# SterUni_V1.net
KiCad netlist of a schematic drawn in Altium Designer
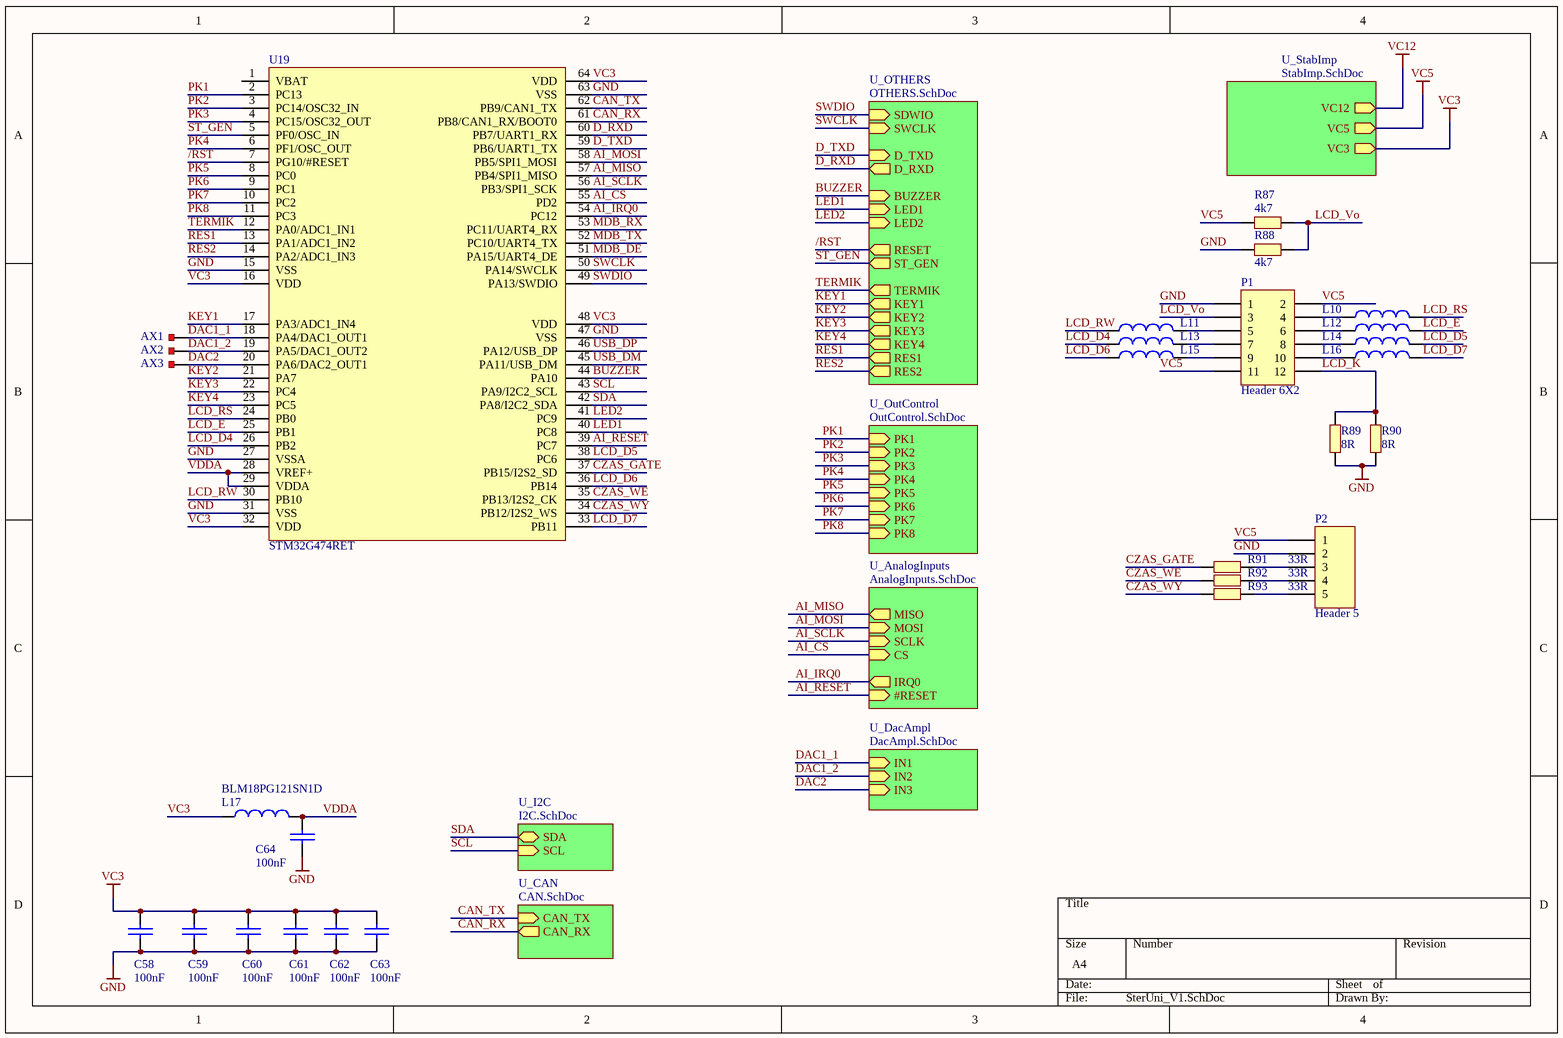
[diagram p0: SterUni_V1.SchDoc]

(export (version "E")
  (design (tool "Eeschema 10.0.6"))
  (components
    (comp (ref "AX1") (value "~") (footprint "PP_SMD4") (libsource (lib "*") (part "PP_RT")))
    (comp (ref "AX2") (value "~") (footprint "PP_SMD4") (libsource (lib "*") (part "PP_RT")))
    (comp (ref "AX3") (value "~") (footprint "PP_SMD4") (libsource (lib "*") (part "PP_RT")))
    (comp (ref "C58")
      (value "100nF")
      (footprint "0603C")
      (description "Capacitor")
      (libsource (lib "*") (part "CAP"))
    )
    (comp (ref "C59")
      (value "100nF")
      (footprint "0603C")
      (description "Capacitor")
      (libsource (lib "*") (part "CAP"))
    )
    (comp (ref "C60")
      (value "100nF")
      (footprint "0603C")
      (description "Capacitor")
      (libsource (lib "*") (part "CAP"))
    )
    (comp (ref "C61")
      (value "100nF")
      (footprint "0603C")
      (description "Capacitor")
      (libsource (lib "*") (part "CAP"))
    )
    (comp (ref "C62")
      (value "100nF")
      (footprint "0603C")
      (description "Capacitor")
      (libsource (lib "*") (part "CAP"))
    )
    (comp (ref "C63")
      (value "100nF")
      (footprint "0603C")
      (description "Capacitor")
      (libsource (lib "*") (part "CAP"))
    )
    (comp (ref "C64")
      (value "100nF")
      (footprint "0603C")
      (description "Capacitor")
      (libsource (lib "*") (part "CAP"))
    )
    (comp (ref "L10")
      (value "BLM18PG121SN1D")
      (footprint "0603L")
      (description "Bead,120R,2A,0603,BLM18PG121SN1D,MURATA")
      (libsource (lib "MCD_TOOLS") (part "BEAD_120R_2A_0603"))
    )
    (comp (ref "L11")
      (value "BLM18PG121SN1D")
      (footprint "0603L")
      (description "Bead,120R,2A,0603,BLM18PG121SN1D,MURATA")
      (libsource (lib "MCD_TOOLS") (part "BEAD_120R_2A_0603"))
    )
    (comp (ref "L12")
      (value "BLM18PG121SN1D")
      (footprint "0603L")
      (description "Bead,120R,2A,0603,BLM18PG121SN1D,MURATA")
      (libsource (lib "MCD_TOOLS") (part "BEAD_120R_2A_0603"))
    )
    (comp (ref "L13")
      (value "BLM18PG121SN1D")
      (footprint "0603L")
      (description "Bead,120R,2A,0603,BLM18PG121SN1D,MURATA")
      (libsource (lib "MCD_TOOLS") (part "BEAD_120R_2A_0603"))
    )
    (comp (ref "L14")
      (value "BLM18PG121SN1D")
      (footprint "0603L")
      (description "Bead,120R,2A,0603,BLM18PG121SN1D,MURATA")
      (libsource (lib "MCD_TOOLS") (part "BEAD_120R_2A_0603"))
    )
    (comp (ref "L15")
      (value "BLM18PG121SN1D")
      (footprint "0603L")
      (description "Bead,120R,2A,0603,BLM18PG121SN1D,MURATA")
      (libsource (lib "MCD_TOOLS") (part "BEAD_120R_2A_0603"))
    )
    (comp (ref "L16")
      (value "BLM18PG121SN1D")
      (footprint "0603L")
      (description "Bead,120R,2A,0603,BLM18PG121SN1D,MURATA")
      (libsource (lib "MCD_TOOLS") (part "BEAD_120R_2A_0603"))
    )
    (comp (ref "L17")
      (value "BLM18PG121SN1D")
      (footprint "0603L")
      (description "Bead,120R,2A,0603,BLM18PG121SN1D,MURATA")
      (libsource (lib "MCD_TOOLS") (part "BEAD_120R_2A_0603"))
    )
    (comp (ref "P1")
      (value "Header 6X2")
      (footprint "UMATCH-12")
      (description "Header, 6-Pin, Dual row")
      (fields (field (name "PUBLISHER") "Altium Limited"))
      (libsource (lib "Miscellaneous Connectors") (part "Header 6X2"))
    )
    (comp (ref "P2")
      (value "Header 5")
      (footprint "JST-B5B-XH-A")
      (description "Header, 5-Pin")
      (fields (field (name "PUBLISHER") "Altium Limited"))
      (libsource (lib "Miscellaneous Connectors") (part "Header 5"))
    )
    (comp (ref "R87") (value "4k7") (footprint "0603R") (libsource (lib "*") (part "RES3")))
    (comp (ref "R88") (value "4k7") (footprint "0603R") (libsource (lib "*") (part "RES3")))
    (comp (ref "R89") (value "8R") (footprint "1206") (libsource (lib "") (part "RES3_1")))
    (comp (ref "R90") (value "8R") (footprint "1206") (libsource (lib "") (part "RES3_1")))
    (comp (ref "R91") (value "33R") (footprint "0603R") (libsource (lib "*") (part "RES3")))
    (comp (ref "R92") (value "33R") (footprint "0603R") (libsource (lib "*") (part "RES3")))
    (comp (ref "R93") (value "33R") (footprint "0603R") (libsource (lib "*") (part "RES3")))
    (comp (ref "U19")
      (value "STM32G474RET")
      (footprint "LQFP64")
      (libsource (lib "GkSchlib") (part "STM32FG474RET"))
    )
  )
  (nets
    (net (code "1") (name "/AI_CS") (class "Default")
      (node (ref "U19") (pin "55") (pinfunction "PD2_55") (pintype "passive"))
    )
    (net (code "2") (name "/AI_IRQ0") (class "Default")
      (node (ref "U19") (pin "54") (pinfunction "PC12_54") (pintype "passive"))
    )
    (net (code "3") (name "/AI_MISO") (class "Default")
      (node (ref "U19") (pin "57") (pinfunction "PB4/SPI1_MISO_57") (pintype "passive"))
    )
    (net (code "4") (name "/AI_MOSI") (class "Default")
      (node (ref "U19") (pin "58") (pinfunction "PB5/SPI1_MOSI_58") (pintype "passive"))
    )
    (net (code "5") (name "/AI_RESET") (class "Default")
      (node (ref "U19") (pin "39") (pinfunction "PC7_39") (pintype "passive"))
    )
    (net (code "6") (name "/AI_SCLK") (class "Default")
      (node (ref "U19") (pin "56") (pinfunction "PB3/SPI1_SCK_56") (pintype "passive"))
    )
    (net (code "7") (name "/BUZZER") (class "Default")
      (node (ref "U19") (pin "44") (pinfunction "PA10_44") (pintype "passive"))
    )
    (net (code "8") (name "/CAN_RX") (class "Default")
      (node (ref "U19") (pin "61") (pinfunction "PB8/CAN1_RX/BOOT0_61") (pintype "passive"))
    )
    (net (code "9") (name "/CAN_TX") (class "Default")
      (node (ref "U19") (pin "62") (pinfunction "PB9/CAN1_TX_62") (pintype "passive"))
    )
    (net (code "10") (name "/CZAS_GATE") (class "Default")
      (node (ref "R91") (pin "2") (pintype "passive"))
      (node (ref "U19") (pin "37") (pinfunction "PB15/I2S2_SD_37") (pintype "passive"))
    )
    (net (code "11") (name "/CZAS_WE") (class "Default")
      (node (ref "R92") (pin "2") (pintype "passive"))
      (node (ref "U19") (pin "35") (pinfunction "PB13/I2S2_CK_35") (pintype "passive"))
    )
    (net (code "12") (name "/CZAS_WY") (class "Default")
      (node (ref "R93") (pin "2") (pintype "passive"))
      (node (ref "U19") (pin "34") (pinfunction "PB12/I2S2_WS_34") (pintype "passive"))
    )
    (net (code "13") (name "/DAC1_1") (class "Default")
      (node (ref "AX1") (pin "1") (pintype "passive"))
      (node (ref "U19") (pin "18") (pinfunction "PA4/DAC1_OUT1_18") (pintype "passive"))
    )
    (net (code "14") (name "/DAC1_2") (class "Default")
      (node (ref "AX2") (pin "1") (pintype "passive"))
      (node (ref "U19") (pin "19") (pinfunction "PA5/DAC1_OUT2_19") (pintype "passive"))
    )
    (net (code "15") (name "/DAC2") (class "Default")
      (node (ref "AX3") (pin "1") (pintype "passive"))
      (node (ref "U19") (pin "20") (pinfunction "PA6/DAC2_OUT1_20") (pintype "passive"))
    )
    (net (code "16") (name "/D_RXD") (class "Default")
      (node (ref "U19") (pin "60") (pinfunction "PB7/UART1_RX_60") (pintype "passive"))
    )
    (net (code "17") (name "/D_TXD") (class "Default")
      (node (ref "U19") (pin "59") (pinfunction "PB6/UART1_TX_59") (pintype "passive"))
    )
    (net (code "18") (name "/KEY1") (class "Default")
      (node (ref "U19") (pin "17") (pinfunction "PA3/ADC1_IN4_17") (pintype "passive"))
    )
    (net (code "19") (name "/KEY2") (class "Default")
      (node (ref "U19") (pin "21") (pinfunction "PA7_21") (pintype "passive"))
    )
    (net (code "20") (name "/KEY3") (class "Default")
      (node (ref "U19") (pin "22") (pinfunction "PC4_22") (pintype "passive"))
    )
    (net (code "21") (name "/KEY4") (class "Default")
      (node (ref "U19") (pin "23") (pinfunction "PC5_23") (pintype "passive"))
    )
    (net (code "22") (name "/LCD_D4") (class "Default")
      (node (ref "L13") (pin "1") (pinfunction "1_1") (pintype "passive"))
      (node (ref "U19") (pin "26") (pinfunction "PB2_26") (pintype "passive"))
    )
    (net (code "23") (name "/LCD_D5") (class "Default")
      (node (ref "L14") (pin "2") (pinfunction "2_2") (pintype "passive"))
      (node (ref "U19") (pin "38") (pinfunction "PC6_38") (pintype "passive"))
    )
    (net (code "24") (name "/LCD_D6") (class "Default")
      (node (ref "L15") (pin "1") (pinfunction "1_1") (pintype "passive"))
      (node (ref "U19") (pin "36") (pinfunction "PB14_36") (pintype "passive"))
    )
    (net (code "25") (name "/LCD_D7") (class "Default")
      (node (ref "L16") (pin "2") (pinfunction "2_2") (pintype "passive"))
      (node (ref "U19") (pin "33") (pinfunction "PB11_33") (pintype "passive"))
    )
    (net (code "26") (name "/LCD_E") (class "Default")
      (node (ref "L12") (pin "2") (pinfunction "2_2") (pintype "passive"))
      (node (ref "U19") (pin "25") (pinfunction "PB1_25") (pintype "passive"))
    )
    (net (code "27") (name "/LCD_K") (class "Default")
      (node (ref "P1") (pin "12") (pinfunction "12_12") (pintype "passive"))
      (node (ref "R89") (pin "1") (pintype "passive"))
      (node (ref "R90") (pin "1") (pintype "passive"))
    )
    (net (code "28") (name "/LCD_RS") (class "Default")
      (node (ref "L10") (pin "2") (pinfunction "2_2") (pintype "passive"))
      (node (ref "U19") (pin "24") (pinfunction "PB0_24") (pintype "passive"))
    )
    (net (code "29") (name "/LCD_RW") (class "Default")
      (node (ref "L11") (pin "1") (pinfunction "1_1") (pintype "passive"))
      (node (ref "U19") (pin "30") (pinfunction "PB10_30") (pintype "passive"))
    )
    (net (code "30") (name "/LCD_Vo") (class "Default")
      (node (ref "P1") (pin "3") (pinfunction "3_3") (pintype "passive"))
      (node (ref "R87") (pin "1") (pintype "passive"))
      (node (ref "R88") (pin "1") (pintype "passive"))
    )
    (net (code "31") (name "/LED1") (class "Default")
      (node (ref "U19") (pin "40") (pinfunction "PC8_40") (pintype "passive"))
    )
    (net (code "32") (name "/LED2") (class "Default")
      (node (ref "U19") (pin "41") (pinfunction "PC9_41") (pintype "passive"))
    )
    (net (code "33") (name "/MDB_DE") (class "Default")
      (node (ref "U19") (pin "51") (pinfunction "PA15/UART4_DE_51") (pintype "passive"))
    )
    (net (code "34") (name "/MDB_RX") (class "Default")
      (node (ref "U19") (pin "53") (pinfunction "PC11/UART4_RX_53") (pintype "passive"))
    )
    (net (code "35") (name "/MDB_TX") (class "Default")
      (node (ref "U19") (pin "52") (pinfunction "PC10/UART4_TX_52") (pintype "passive"))
    )
    (net (code "36") (name "/PK1") (class "Default")
      (node (ref "U19") (pin "2") (pinfunction "PC13_2") (pintype "passive"))
    )
    (net (code "37") (name "/PK2") (class "Default")
      (node (ref "U19") (pin "3") (pinfunction "PC14/OSC32_IN_3") (pintype "passive"))
    )
    (net (code "38") (name "/PK3") (class "Default")
      (node (ref "U19") (pin "4") (pinfunction "PC15/OSC32_OUT_4") (pintype "passive"))
    )
    (net (code "39") (name "/PK4") (class "Default")
      (node (ref "U19") (pin "6") (pinfunction "PF1/OSC_OUT_6") (pintype "passive"))
    )
    (net (code "40") (name "/PK5") (class "Default")
      (node (ref "U19") (pin "8") (pinfunction "PC0_8") (pintype "passive"))
    )
    (net (code "41") (name "/PK6") (class "Default")
      (node (ref "U19") (pin "9") (pinfunction "PC1_9") (pintype "passive"))
    )
    (net (code "42") (name "/PK7") (class "Default")
      (node (ref "U19") (pin "10") (pinfunction "PC2_10") (pintype "passive"))
    )
    (net (code "43") (name "/PK8") (class "Default")
      (node (ref "U19") (pin "11") (pinfunction "PC3_11") (pintype "passive"))
    )
    (net (code "44") (name "/RES1") (class "Default")
      (node (ref "U19") (pin "13") (pinfunction "PA1/ADC1_IN2_13") (pintype "passive"))
    )
    (net (code "45") (name "/RES2") (class "Default")
      (node (ref "U19") (pin "14") (pinfunction "PA2/ADC1_IN3_14") (pintype "passive"))
    )
    (net (code "46") (name "/SCL") (class "Default")
      (node (ref "U19") (pin "43") (pinfunction "PA9/I2C2_SCL_43") (pintype "passive"))
    )
    (net (code "47") (name "/SDA") (class "Default")
      (node (ref "U19") (pin "42") (pinfunction "PA8/I2C2_SDA_42") (pintype "passive"))
    )
    (net (code "48") (name "/ST_GEN") (class "Default")
      (node (ref "U19") (pin "5") (pinfunction "PF0/OSC_IN_5") (pintype "passive"))
    )
    (net (code "49") (name "/SWCLK") (class "Default")
      (node (ref "U19") (pin "50") (pinfunction "PA14/SWCLK_50") (pintype "passive"))
    )
    (net (code "50") (name "/SWDIO") (class "Default")
      (node (ref "U19") (pin "49") (pinfunction "PA13/SWDIO_49") (pintype "passive"))
    )
    (net (code "51") (name "/TERMIK") (class "Default")
      (node (ref "U19") (pin "12") (pinfunction "PA0/ADC1_IN1_12") (pintype "passive"))
    )
    (net (code "52") (name "/USB_DM") (class "Default")
      (node (ref "U19") (pin "45") (pinfunction "PA11/USB_DM_45") (pintype "passive"))
    )
    (net (code "53") (name "/USB_DP") (class "Default")
      (node (ref "U19") (pin "46") (pinfunction "PA12/USB_DP_46") (pintype "passive"))
    )
    (net (code "54") (name "/VDDA") (class "Default")
      (node (ref "C64") (pin "1") (pinfunction "1_1") (pintype "passive"))
      (node (ref "L17") (pin "2") (pinfunction "2_2") (pintype "passive"))
      (node (ref "U19") (pin "28") (pinfunction "VREF+_28") (pintype "passive"))
      (node (ref "U19") (pin "29") (pinfunction "VDDA_29") (pintype "passive"))
    )
    (net (code "55") (name "/{slash}RST") (class "Default")
      (node (ref "U19") (pin "7") (pinfunction "PG10/#RESET_7") (pintype "passive"))
    )
    (net (code "56") (name "GND") (class "Default")
      (node (ref "C58") (pin "2") (pinfunction "2_2") (pintype "passive"))
      (node (ref "C59") (pin "2") (pinfunction "2_2") (pintype "passive"))
      (node (ref "C60") (pin "2") (pinfunction "2_2") (pintype "passive"))
      (node (ref "C61") (pin "2") (pinfunction "2_2") (pintype "passive"))
      (node (ref "C62") (pin "2") (pinfunction "2_2") (pintype "passive"))
      (node (ref "C63") (pin "2") (pinfunction "2_2") (pintype "passive"))
      (node (ref "C64") (pin "2") (pinfunction "2_2") (pintype "passive"))
      (node (ref "P1") (pin "1") (pinfunction "1_1") (pintype "passive"))
      (node (ref "P2") (pin "2") (pinfunction "2_2") (pintype "passive"))
      (node (ref "R88") (pin "2") (pintype "passive"))
      (node (ref "R89") (pin "2") (pintype "passive"))
      (node (ref "R90") (pin "2") (pintype "passive"))
      (node (ref "U19") (pin "15") (pinfunction "VSS_15") (pintype "passive"))
      (node (ref "U19") (pin "27") (pinfunction "VSSA_27") (pintype "passive"))
      (node (ref "U19") (pin "31") (pinfunction "VSS_31") (pintype "passive"))
      (node (ref "U19") (pin "47") (pinfunction "VSS_47") (pintype "passive"))
      (node (ref "U19") (pin "63") (pinfunction "VSS_63") (pintype "passive"))
    )
    (net (code "57") (name "Net-(L10-Pad1)") (class "Default")
      (node (ref "L10") (pin "1") (pinfunction "1_1") (pintype "passive"))
      (node (ref "P1") (pin "4") (pinfunction "4_4") (pintype "passive"))
    )
    (net (code "58") (name "Net-(L11-Pad2)") (class "Default")
      (node (ref "L11") (pin "2") (pinfunction "2_2") (pintype "passive"))
      (node (ref "P1") (pin "5") (pinfunction "5_5") (pintype "passive"))
    )
    (net (code "59") (name "Net-(L12-Pad1)") (class "Default")
      (node (ref "L12") (pin "1") (pinfunction "1_1") (pintype "passive"))
      (node (ref "P1") (pin "6") (pinfunction "6_6") (pintype "passive"))
    )
    (net (code "60") (name "Net-(L13-Pad2)") (class "Default")
      (node (ref "L13") (pin "2") (pinfunction "2_2") (pintype "passive"))
      (node (ref "P1") (pin "7") (pinfunction "7_7") (pintype "passive"))
    )
    (net (code "61") (name "Net-(L14-Pad1)") (class "Default")
      (node (ref "L14") (pin "1") (pinfunction "1_1") (pintype "passive"))
      (node (ref "P1") (pin "8") (pinfunction "8_8") (pintype "passive"))
    )
    (net (code "62") (name "Net-(L15-Pad2)") (class "Default")
      (node (ref "L15") (pin "2") (pinfunction "2_2") (pintype "passive"))
      (node (ref "P1") (pin "9") (pinfunction "9_9") (pintype "passive"))
    )
    (net (code "63") (name "Net-(L16-Pad1)") (class "Default")
      (node (ref "L16") (pin "1") (pinfunction "1_1") (pintype "passive"))
      (node (ref "P1") (pin "10") (pinfunction "10_10") (pintype "passive"))
    )
    (net (code "64") (name "Net-(P2-Pad3)") (class "Default")
      (node (ref "P2") (pin "3") (pinfunction "3_3") (pintype "passive"))
      (node (ref "R91") (pin "1") (pintype "passive"))
    )
    (net (code "65") (name "Net-(P2-Pad4)") (class "Default")
      (node (ref "P2") (pin "4") (pinfunction "4_4") (pintype "passive"))
      (node (ref "R92") (pin "1") (pintype "passive"))
    )
    (net (code "66") (name "Net-(P2-Pad5)") (class "Default")
      (node (ref "P2") (pin "5") (pinfunction "5_5") (pintype "passive"))
      (node (ref "R93") (pin "1") (pintype "passive"))
    )
    (net (code "67") (name "VC3") (class "Default")
      (node (ref "C58") (pin "1") (pinfunction "1_1") (pintype "passive"))
      (node (ref "C59") (pin "1") (pinfunction "1_1") (pintype "passive"))
      (node (ref "C60") (pin "1") (pinfunction "1_1") (pintype "passive"))
      (node (ref "C61") (pin "1") (pinfunction "1_1") (pintype "passive"))
      (node (ref "C62") (pin "1") (pinfunction "1_1") (pintype "passive"))
      (node (ref "C63") (pin "1") (pinfunction "1_1") (pintype "passive"))
      (node (ref "L17") (pin "1") (pinfunction "1_1") (pintype "passive"))
      (node (ref "U19") (pin "16") (pinfunction "VDD_16") (pintype "passive"))
      (node (ref "U19") (pin "32") (pinfunction "VDD_32") (pintype "passive"))
      (node (ref "U19") (pin "48") (pinfunction "VDD_48") (pintype "passive"))
      (node (ref "U19") (pin "64") (pinfunction "VDD_64") (pintype "passive"))
    )
    (net (code "68") (name "VC5") (class "Default")
      (node (ref "P1") (pin "11") (pinfunction "11_11") (pintype "passive"))
      (node (ref "P1") (pin "2") (pinfunction "2_2") (pintype "passive"))
      (node (ref "P2") (pin "1") (pinfunction "1_1") (pintype "passive"))
      (node (ref "R87") (pin "2") (pintype "passive"))
    )
    (net (code "70") (name "unconnected-(U19-VBAT-Pad1)") (class "Default")
      (node (ref "U19") (pin "1") (pinfunction "VBAT_1") (pintype "passive"))
    )
  )
)
